# Main.net
KiCad netlist of a schematic drawn in Altium Designer
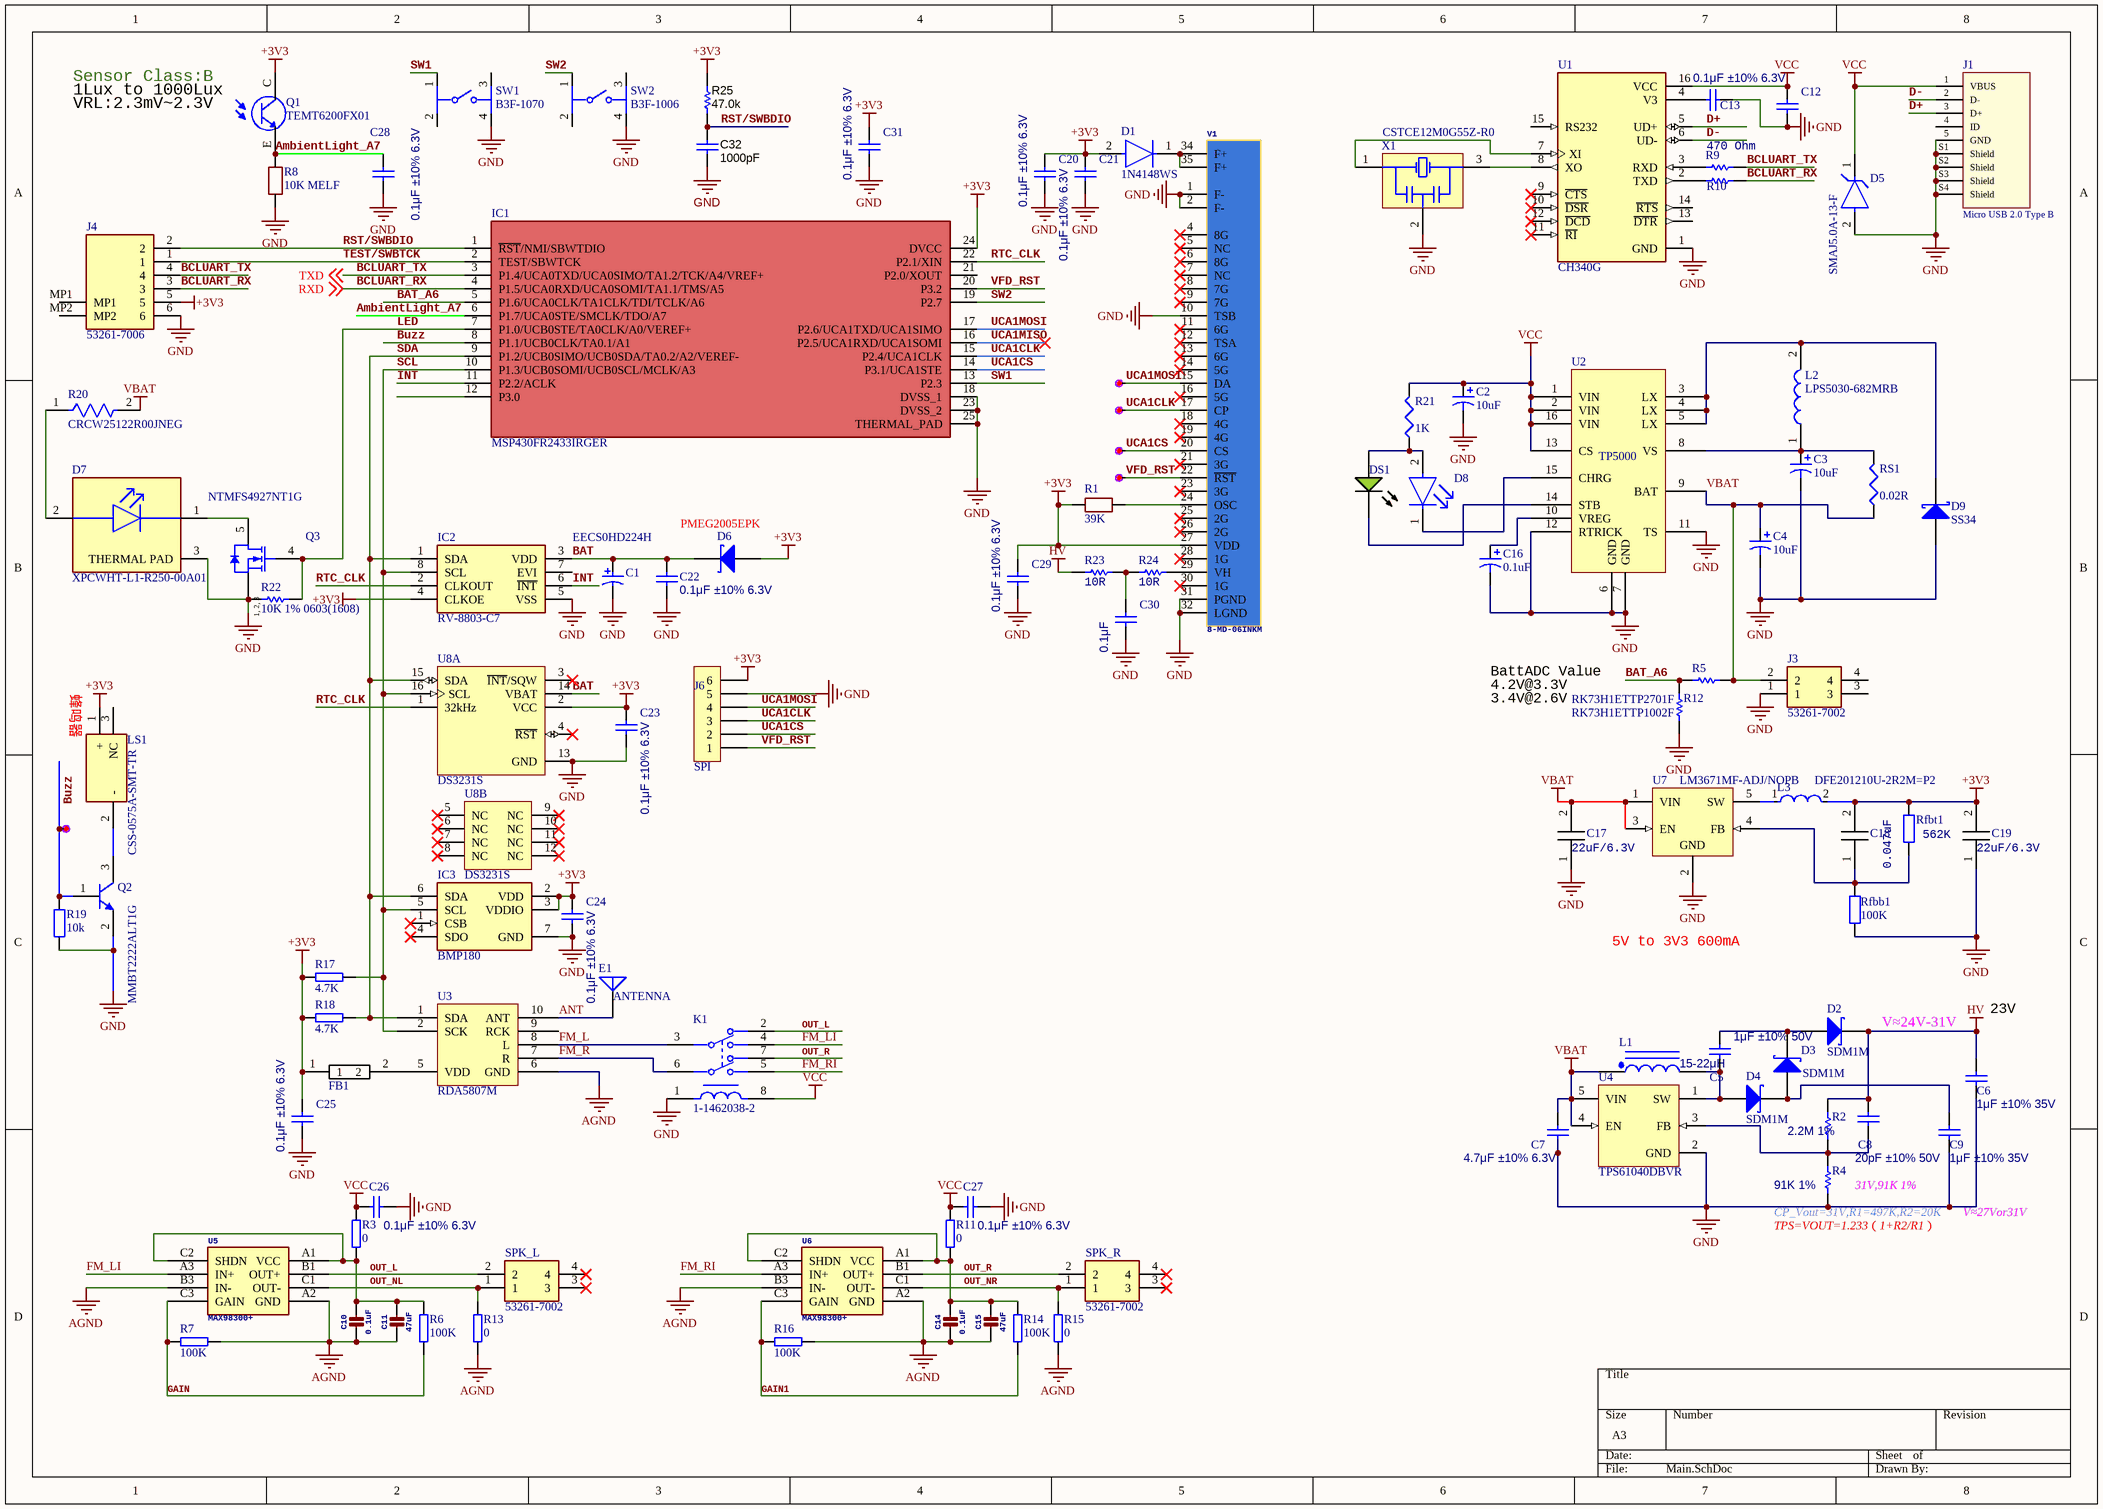
[diagram p0: Main.SchDoc]

(export (version "E")
  (design (tool "Eeschema 10.0.6"))
  (components
    (comp (ref "C1")
      (value "EECS0HD224H")
      (footprint "PNSC-EECS0HD224H")
      (description "Stacked Coin Type Capacitor, 0.22 F, +/- 80%, 5.5 VDC, -25 to 70 degC, 2-Pin THD, RoHS, Bulk")
      (fields (field (name "MANUFACTURER") "Panasonic") (field (name "TOLERANCE") "-20%,+80%"))
      (libsource (lib "Altium Content Vault") (part "CAP-P-2"))
    )
    (comp (ref "C2")
      (value "10uF")
      (footprint "1210")
      (description "Polarized Capacitor (Surface Mount)")
      (fields (field (name "Comment") "Cap Pol3") (field (name "PUBLISHER") "Altium Limited"))
      (libsource (lib "Miscellaneous Devices") (part "Cap Pol3"))
    )
    (comp (ref "C3")
      (value "10uF")
      (footprint "1206")
      (description "Polarized Capacitor (Surface Mount)")
      (fields (field (name "Comment") "Cap Pol3") (field (name "PUBLISHER") "Altium Limited"))
      (libsource (lib "Miscellaneous Devices") (part "Cap Pol3"))
    )
    (comp (ref "C4")
      (value "10uF")
      (footprint "1206")
      (description "Polarized Capacitor (Surface Mount)")
      (fields (field (name "Comment") "Cap Pol3") (field (name "PUBLISHER") "Altium Limited"))
      (libsource (lib "Miscellaneous Devices") (part "Cap Pol3"))
    )
    (comp (ref "C5")
      (value "1μF ±10% 50V")
      (footprint "0402 CAP - s")
      (description "Cap0402,CL05A105KQ5NNNC C52923")
      (libsource (lib "FTJ") (part "Cap SMD"))
    )
    (comp (ref "C6")
      (value "1μF ±10% 35V")
      (footprint "0603 cap - S")
      (description "Cap 0603")
      (libsource (lib "FTJ") (part "Cap SMD"))
    )
    (comp (ref "C7")
      (value "4.7μF ±10% 6.3V")
      (footprint "0402 Cap - S")
      (description "Cap 0603")
      (libsource (lib "FTJ") (part "Cap SMD"))
    )
    (comp (ref "C8")
      (value "20pF ±10% 50V")
      (footprint "0402 CAP - s")
      (description "Cap0402,CL05A105KQ5NNNC C52923")
      (libsource (lib "FTJ") (part "Cap SMD"))
    )
    (comp (ref "C9")
      (value "1μF ±10% 35V")
      (footprint "0402 Cap - S")
      (description "Cap 0603")
      (libsource (lib "FTJ") (part "Cap SMD"))
    )
    (comp (ref "C10")
      (value "0.1uF")
      (footprint "0201")
      (libsource (lib "Metro Mini Rev A") (part "CAP_CERAMIC_0805MP"))
    )
    (comp (ref "C11")
      (value "47uF")
      (footprint "_0805MP")
      (libsource (lib "Metro Mini Rev A") (part "CAP_CERAMIC_0805MP"))
    )
    (comp (ref "C12")
      (value "0.1μF ±10% 6.3V")
      (footprint "0603 cap - S")
      (description "Cap 0603")
      (libsource (lib "FTJ") (part "Cap SMD"))
    )
    (comp (ref "C13")
      (value "0.1μF ±10% 6.3V")
      (footprint "0603 cap - S")
      (description "Cap 0603")
      (libsource (lib "FTJ") (part "Cap SMD"))
    )
    (comp (ref "C14")
      (value "0.1uF")
      (footprint "0201")
      (libsource (lib "Metro Mini Rev A") (part "CAP_CERAMIC_0805MP"))
    )
    (comp (ref "C15")
      (value "47uF")
      (footprint "_0805MP")
      (libsource (lib "Metro Mini Rev A") (part "CAP_CERAMIC_0805MP"))
    )
    (comp (ref "C16")
      (value "0.1uF")
      (footprint "0603")
      (description "Polarized Capacitor (Surface Mount)")
      (fields (field (name "Comment") "Cap Pol3") (field (name "PUBLISHER") "Altium Limited"))
      (libsource (lib "Miscellaneous Devices") (part "Cap Pol3"))
    )
    (comp (ref "C17")
      (value "22uF/6.3V")
      (footprint "0603-CAP")
      (fields
        (field (name "MANUFACTURER_PART_NUMBER") "ZRB18AR61A226ME01L")
        (field (name "Comment") "GRM188R60J226ME15D")
      )
      (libsource (lib "*") (part "ZRB18AR61A226ME01L"))
    )
    (comp (ref "C18")
      (value "0.047uF")
      (footprint "0201")
      (description "CAP, CERM, 0.047uF, 10V, ±10%, X7R, 0201")
      (fields
        (field (name "MANUFACTURER_PART_NUMBER") "GRM155R71E473KA88D")
        (field (name "MOUSER PART NUMBER") "81-GRM155R71E473KA88")
      )
      (libsource (lib "*") (part "GRM155R71E473KA88D"))
    )
    (comp (ref "C19")
      (value "22uF/6.3V")
      (footprint "0603-CAP")
      (fields
        (field (name "MANUFACTURER_PART_NUMBER") "ZRB18AR61A226ME01L")
        (field (name "Comment") "GRM188R60J226ME15D")
      )
      (libsource (lib "*") (part "ZRB18AR61A226ME01L"))
    )
    (comp (ref "C20")
      (value "0.1μF ±10% 6.3V")
      (footprint "0603 cap - S")
      (description "Cap 0603")
      (libsource (lib "FTJ") (part "Cap SMD"))
    )
    (comp (ref "C21")
      (value "0.1μF ±10% 6.3V")
      (footprint "0603 cap - S")
      (description "Cap 0603")
      (libsource (lib "FTJ") (part "Cap SMD"))
    )
    (comp (ref "C22")
      (value "0.1μF ±10% 6.3V")
      (footprint "0603 cap - S")
      (description "Cap 0603")
      (libsource (lib "FTJ") (part "Cap SMD"))
    )
    (comp (ref "C23")
      (value "0.1μF ±10% 6.3V")
      (footprint "0603 cap - S")
      (description "Cap 0603")
      (libsource (lib "FTJ") (part "Cap SMD"))
    )
    (comp (ref "C24")
      (value "0.1μF ±10% 6.3V")
      (footprint "0603 cap - S")
      (description "Cap 0603")
      (libsource (lib "FTJ") (part "Cap SMD"))
    )
    (comp (ref "C25")
      (value "0.1μF ±10% 6.3V")
      (footprint "0603 cap - S")
      (description "Cap 0603")
      (libsource (lib "FTJ") (part "Cap SMD"))
    )
    (comp (ref "C26")
      (value "0.1μF ±10% 6.3V")
      (footprint "0603 cap - S")
      (description "Cap 0603")
      (libsource (lib "FTJ") (part "Cap SMD"))
    )
    (comp (ref "C27")
      (value "0.1μF ±10% 6.3V")
      (footprint "0603 cap - S")
      (description "Cap 0603")
      (libsource (lib "FTJ") (part "Cap SMD"))
    )
    (comp (ref "C28")
      (value "0.1μF ±10% 6.3V")
      (footprint "0603 cap - S")
      (description "Cap 0603")
      (libsource (lib "FTJ") (part "Cap SMD"))
    )
    (comp (ref "C29")
      (value "0.1μF ±10% 6.3V")
      (footprint "0603 cap - S")
      (description "Cap 0603")
      (libsource (lib "FTJ") (part "Cap SMD"))
    )
    (comp (ref "C30")
      (value "0.1μF")
      (footprint "0603 cap - S")
      (description "Cap 0603")
      (libsource (lib "FTJ") (part "Cap SMD"))
    )
    (comp (ref "C31")
      (value "0.1μF ±10% 6.3V")
      (footprint "0603 cap - S")
      (description "Cap 0603")
      (libsource (lib "FTJ") (part "Cap SMD"))
    )
    (comp (ref "C32")
      (value "GRM155R71H102KA01D")
      (footprint "0402")
      (description "CAP, CERM, 1000 pF, 50 V, +/- 10%, X7R, 0402")
      (fields
        (field (name "VALUEDISPLAYED") "1000pF")
        (field (name "MANUFACTURER") "MuRata")
        (field (name "PUBLISHER") "Texas Instruments")
      )
      (libsource (lib "Capacitor_Ceramic") (part "GRM155R71H102KA01D"))
    )
    (comp (ref "D1")
      (value "1N4148WS")
      (footprint "FP-477AB-IPC_C")
      (description "DIODE GEN PURP 75V 150MA SOD323F")
      (libsource (lib "Altium Content Vault") (part "d7152d700b627762746794eb795d46e"))
    )
    (comp (ref "D2")
      (value "SDM1M")
      (footprint "DFN1608-2-UDFN1608")
      (description "Schotty Diodes")
      (libsource (lib "FTJ") (part "Diode_Schotty"))
    )
    (comp (ref "D3")
      (value "SDM1M")
      (footprint "DFN1608-2-UDFN1608")
      (description "Schotty Diodes")
      (libsource (lib "FTJ") (part "Diode_Schotty"))
    )
    (comp (ref "D4")
      (value "SDM1M")
      (footprint "DFN1608-2-UDFN1608")
      (description "Schotty Diodes")
      (libsource (lib "FTJ") (part "Diode_Schotty"))
    )
    (comp (ref "D5")
      (value "SMAJ5.0A-13-F")
      (footprint "FP-SMA-MFG")
      (description "TVS DIODE 5V 9.2V SMA")
      (fields
        (field (name "MANUFACTURER") "Diodes Inc.")
        (field (name "OCTOPART") "https://octopart.com/smaj5.0a-13-f-diodes+inc.-350158")
      )
      (libsource (lib "Altium Content Vault") (part "f813f71cba58e380607f5dd3caf9714"))
    )
    (comp (ref "D6")
      (value "PMEG2005EPK")
      (footprint "DFN1608-2-UDFN1608")
      (description "Schotty Diodes")
      (libsource (lib "FTJ") (part "Diode_Schotty"))
    )
    (comp (ref "D7")
      (value "XPCWHT-L1-R250-00A01")
      (footprint "FP-XPCWHT-MFG")
      (description "LED XLAMP COOL WHITE 70CRI 2SMD")
      (fields
        (field (name "OCTOPART") "https://octopart.com/xpcwht-l1-r250-00a01-cree-9519579")
        (field (name "MANUFACTURER") "Cree Inc.")
      )
      (libsource (lib "Altium Content Vault") (part "a9d0dd8659a82a27d4251d925192800"))
    )
    (comp (ref "D8")
      (value "VLMW1300-GS08")
      (footprint "FP-6_541-5091_01-4-MFG")
      (description "LED COOL WHITE 0603 SMD")
      (fields
        (field (name "MANUFACTURER") "Vishay")
        (field (name "OCTOPART") "https://octopart.com/vlmw1300-gs08-vishay-21709203")
      )
      (libsource (lib "Altium Content Vault") (part "8706943c75ba83719d021d2fdc84c58"))
    )
    (comp (ref "D9")
      (value "SS34")
      (footprint "SMB")
      (description "Schottky Diode")
      (fields (field (name "PUBLISHER") "Altium Limited"))
      (libsource (lib "Miscellaneous Devices") (part "D Schottky"))
    )
    (comp (ref "DS1")
      (value "ASMT-RF45-AN002")
      (footprint "AVAG-ASMT-RF45_V")
      (description "LED Yellow - Green, 48 mW, 20 mA, -40 to 100 degC, 2-Pin SMD, RoHS, Tape and Reel")
      (fields (field (name "MANUFACTURER") "Avago"))
      (libsource (lib "Altium Content Vault") (part "LED-YELLOW-GREEN-AK-2"))
    )
    (comp (ref "E1")
      (value "ANTENNA")
      (footprint "P125-B")
      (description "Generic Antenna")
      (libsource (lib "Integrated_Library1") (part "ANTENNA"))
    )
    (comp (ref "FB1")
      (value "MPZ1608S260ATAH0")
      (footprint "BEADC1608X75N")
      (description "Ferrite Bead")
      (fields (field (name "MOUSER PART NUMBER") "810-MPZ1608S260ATAH0"))
      (libsource (lib "STM32F405 general control board_1") (part "MPZ1608S260ATAH0"))
    )
    (comp (ref "IC1")
      (value "MSP430FR2433IRGER")
      (footprint "SamacSys:QFN50P400X400X100-25N-D")
      (description "Integrated Circuit")
      (fields (field (name "MOUSER PART NUMBER") "595-SP430FR2433IRGER"))
      (libsource (lib "SamacSys") (part "MSP430FR2433IRGER"))
    )
    (comp (ref "IC2")
      (value "RV-8803-C7")
      (footprint "SamacSys:RV8803C7")
      (description "Integrated Circuit")
      (libsource (lib "*") (part "RV-8803-C7"))
    )
    (comp (ref "IC3")
      (value "BMP180")
      (footprint "SamacSys:BMP180")
      (description "Integrated Circuit")
      (fields (field (name "MOUSER PART NUMBER") "262-BMP180"))
      (libsource (lib "*") (part "BMP180"))
    )
    (comp (ref "J1")
      (value "Micro USB 2.0 Type B")
      (footprint "629105136821")
      (description "Micro USB 2.0 Type B Horizontal SMT 5 Contacts WR-COM")
      (fields (field (name "PART NUMBER") "629105136821") (field (name "PUBLISHER") "Wurth Elektronik"))
      (libsource (lib "ALTIUM-WR-COM-rev18a") (part "629105136821"))
    )
    (comp (ref "J3")
      (value "53261-7002")
      (footprint "SamacSys:532617002")
      (description "Connector")
      (fields (field (name "MOUSER PART NUMBER") "538-53261-7002"))
      (libsource (lib "*") (part "53261-7002"))
    )
    (comp (ref "J4")
      (value "53261-7006")
      (footprint "MX 1.25-WS-6P")
      (description "Connector")
      (fields (field (name "MOUSER PART NUMBER") "538-53261-7006"))
      (libsource (lib "*") (part "53261-7006"))
    )
    (comp (ref "J6")
      (value "SPI")
      (footprint "SIP6")
      (description "Connector")
      (libsource (lib "9G_SCH") (part "CON6"))
    )
    (comp (ref "K1")
      (value "1-1462038-2")
      (footprint "FP-1-1462038-2-MFG")
      (description "RELAY TELECOM DPDT 2A 4.5V")
      (fields
        (field (name "MANUFACTURER") "TE Connectivity")
        (field (name "OCTOPART") "https://octopart.com/1-1462038-2-te+connectivity-40642255")
      )
      (libsource (lib "Altium Content Vault") (part "f6f6c627aadb73ad41e05903558ffa9"))
    )
    (comp (ref "L1")
      (value "15-22μH")
      (footprint "NRS4012")
      (description "Magnetic-Core Inductor with Winding Polarity Marking")
      (fields (field (name "Comment") "Inductor Iron Dot") (field (name "PUBLISHER") "Altium Limited"))
      (libsource (lib "FTJ") (part "Inductor Iron Dot"))
    )
    (comp (ref "L2")
      (value "LPS5030-682MRB")
      (footprint "RCDQLY:LPS5030")
      (description "Inductor")
      (fields
        (field (name "MANUFACTURER_PART_NUMBER") "LPS5030-562MRB")
        (field (name "MOUSER PART NUMBER") "994-LPS5030-562MRB")
      )
      (libsource (lib "*") (part "LPS5030-562MRB"))
    )
    (comp (ref "L3")
      (value "DFE201210U-2R2M=P2")
      (footprint "FP-DFE201210U-MFG")
      (description "FIXED IND 2.2UH 1.2A 228 MOHM")
      (libsource (lib "Altium Content Vault") (part "725321dda6339637d4d059423bc1c3c"))
    )
    (comp (ref "LS1")
      (value "CSS-0575A-SMT-TR")
      (footprint "SamacSys:CSS0575ASMTTR")
      (description "Loudspeaker or Buzzer")
      (fields (field (name "MOUSER PART NUMBER") "490-CSS-0575A-SMT-TR"))
      (libsource (lib "*") (part "CSS-0575A-SMT-TR"))
    )
    (comp (ref "Q1")
      (value "TEMT6200FX01")
      (footprint "TEMT6200FX01:XDCR_TEMT6200FX01")
      (description "Phototransistors 550nm Top View 0805 (2012 Metric)")
      (fields (field (name "MF") "{'manufacturer': u'Vishay Semiconductor Opto Division'}"))
      (libsource (lib "*") (part "TEMT6200FX01"))
    )
    (comp (ref "Q2")
      (value "MMBT2222ALT1G")
      (footprint "ONSC-SOT-23-3-318-08_V")
      (description "General Purpose Transistor, NPN Silicon, 3-Pin SOT-23, Pb-Free, Tape and Reel")
      (fields (field (name "MANUFACTURER") "On Semiconductor"))
      (libsource (lib "Altium Content Vault") (part "ONSC-NPN-B1E2C3-3"))
    )
    (comp (ref "Q3")
      (value "NTMFS4927NT1G")
      (footprint "ONSC-DFN-5-488AA_V")
      (description "Power MOSFET, 30 V, 38 A, Single N-Channel, 5-Pin DFN, Pb-Free, Tape and Reel")
      (fields (field (name "MANUFACTURER") "On Semiconductor"))
      (libsource (lib "Altium Content Vault") (part "ONSC-NMOS-6_E"))
    )
    (comp (ref "R1")
      (value "39K")
      (footprint "MELF1")
      (description "Resistor")
      (libsource (lib "") (part "RES2_1"))
    )
    (comp (ref "R2")
      (value "2.2M 1%")
      (footprint "0402 res - s")
      (description "Resistor C11702")
      (fields (field (name "PUBLISHER") "Altium Limited"))
      (libsource (lib "Miscellaneous Devices") (part "Res1"))
    )
    (comp (ref "R3")
      (value "0")
      (footprint "0603")
      (description "Resistor")
      (libsource (lib "9G_SCH") (part "RES2"))
    )
    (comp (ref "R4")
      (value "91K 1%")
      (footprint "0402 res - s")
      (description "Resistor C11702")
      (fields (field (name "PUBLISHER") "Altium Limited"))
      (libsource (lib "Miscellaneous Devices") (part "Res1"))
    )
    (comp (ref "R5")
      (value "RK73H1ETTP2701F")
      (footprint "RESC1005X40X25LL10T10")
      (fields (field (name "MANUFACTURER") "KOA Speer"))
      (libsource (lib "Altium Content Vault") (part "RES"))
    )
    (comp (ref "R6")
      (value "100K")
      (footprint "0201")
      (description "Resistor")
      (libsource (lib "9G_SCH") (part "RES2"))
    )
    (comp (ref "R7")
      (value "100K")
      (footprint "0201")
      (description "Resistor")
      (libsource (lib "9G_SCH") (part "RES2"))
    )
    (comp (ref "R8")
      (value "10K MELF")
      (footprint "MELF-R3216-1206")
      (description "Resistor")
      (libsource (lib "") (part "RES2_1"))
    )
    (comp (ref "R9")
      (value "RC0603FR-07470RL")
      (footprint "RESC1608X55X25LL10T15")
      (fields (field (name "RESISTANCE") "470 Ohm"))
      (libsource (lib "Altium Content Vault") (part "RES-2"))
    )
    (comp (ref "R10")
      (value "RC0603FR-07470RL")
      (footprint "RESC1608X55X25LL10T15")
      (libsource (lib "Altium Content Vault") (part "RES-2"))
    )
    (comp (ref "R11")
      (value "0")
      (footprint "0603")
      (description "Resistor")
      (libsource (lib "9G_SCH") (part "RES2"))
    )
    (comp (ref "R12")
      (value "RK73H1ETTP1002F")
      (footprint "RESC1005X40X25NL10T10")
      (fields (field (name "MANUFACTURER") "KOA Speer"))
      (libsource (lib "Altium Content Vault") (part "RES"))
    )
    (comp (ref "R13")
      (value "0")
      (footprint "0201")
      (description "Resistor")
      (libsource (lib "9G_SCH") (part "RES2"))
    )
    (comp (ref "R14")
      (value "100K")
      (footprint "0201")
      (description "Resistor")
      (libsource (lib "9G_SCH") (part "RES2"))
    )
    (comp (ref "R15")
      (value "0")
      (footprint "0201")
      (description "Resistor")
      (libsource (lib "9G_SCH") (part "RES2"))
    )
    (comp (ref "R16")
      (value "100K")
      (footprint "0201")
      (description "Resistor")
      (libsource (lib "9G_SCH") (part "RES2"))
    )
    (comp (ref "R17")
      (value "4.7K")
      (footprint "0603")
      (description "Resistor")
      (libsource (lib "9G_SCH") (part "RES2"))
    )
    (comp (ref "R18")
      (value "4.7K")
      (footprint "0603")
      (description "Resistor")
      (libsource (lib "9G_SCH") (part "RES2"))
    )
    (comp (ref "R19")
      (value "10k")
      (footprint "0603 RES")
      (description "贴片电阻")
      (fields (field (name "版权归属") "源创客"))
      (libsource (lib "3.1   - 电阻-电容-电感") (part "R"))
    )
    (comp (ref "R20")
      (value "CRCW25122R00JNEG")
      (footprint "FP-CRCW2512-e3-IPC_C")
      (description "RES Thick Film, 2Ω, 5%, 1W, 200ppm/°C, 2512")
      (fields (field (name "TOLERANCE") "5%"))
      (libsource (lib "Altium Content Vault") (part "1029c3af85768c4190bb7ad29bc67b5"))
    )
    (comp (ref "R21")
      (value "1K")
      (footprint "0603")
      (description "Resistor")
      (fields (field (name "PUBLISHER") "Altium Limited"))
      (libsource (lib "Miscellaneous Devices") (part "Res3"))
    )
    (comp (ref "R22")
      (value "10K 1% 0603(1608)")
      (footprint "RESC0603(1608)_N")
      (description "10K 0.1W 1% 0603 (1608 Metric)  SMD")
      (fields (field (name "POWER") "0.1 W") (field (name "TOLERANCE") "1 %"))
      (libsource (lib "Altium Content Vault") (part "RES"))
    )
    (comp (ref "R23")
      (value "TNPW060310R0BEEA")
      (footprint "RESC1609X55X30NL10T20")
      (fields (field (name "MANUFACTURER") "Vishay Dale") (field (name "PARAMETER 1") "10R"))
      (libsource (lib "Altium Content Vault") (part "RES"))
    )
    (comp (ref "R24")
      (value "TNPW060310R0BEEA")
      (footprint "RESC1609X55X30NL10T20")
      (fields (field (name "MANUFACTURER") "Vishay Dale") (field (name "PARAMETER 1") "10R"))
      (libsource (lib "Altium Content Vault") (part "RES"))
    )
    (comp (ref "R25")
      (value "RC0402FR-0747KL")
      (footprint "0402")
      (description "RES, 47.0 k, 1%, 0.0625 W, 0402")
      (fields
        (field (name "VALUEDISPLAYED") "47.0k")
        (field (name "MANUFACTURER") "Yageo America")
        (field (name "PUBLISHER") "Texas Instruments")
      )
      (libsource (lib "Resistor_0402") (part "RC0402FR-0747KL"))
    )
    (comp (ref "Rfbb1")
      (value "100K")
      (footprint "0201")
      (description "SMD 1/10Watt 100Kohms 1%")
      (fields (field (name "Comment") "RC0201JR-13100KL"))
      (libsource (lib "Miscellaneous Devices LC") (part "0603 82KΩ (8202) 1%"))
    )
    (comp (ref "Rfbt1")
      (value "RC0201FR-07309KL")
      (footprint "0201")
      (description "贴片电阻562K")
      (fields (field (name "PARAMETER 1") "562K"))
      (libsource (lib "3.1   - 电阻-电容-电感") (part "R"))
    )
    (comp (ref "RS1")
      (value "0.02R")
      (footprint "1206")
      (description "Resistor")
      (fields (field (name "PUBLISHER") "Altium Limited"))
      (libsource (lib "Miscellaneous Devices") (part "Res3"))
    )
    (comp (ref "SPK_L")
      (value "53261-7002")
      (footprint "SamacSys:532617002")
      (description "Connector")
      (fields (field (name "MOUSER PART NUMBER") "538-53261-7002"))
      (libsource (lib "*") (part "53261-7002"))
    )
    (comp (ref "SPK_R")
      (value "53261-7002")
      (footprint "SamacSys:532617002")
      (description "Connector")
      (fields (field (name "MOUSER PART NUMBER") "538-53261-7002"))
      (libsource (lib "*") (part "53261-7002"))
    )
    (comp (ref "SW1")
      (value "B3F-1070")
      (footprint "FP-B3F-1070-MFG")
      (description "SWITCH TACTILE SPST-NO 0.05A 24V")
      (libsource (lib "Altium Content Vault") (part "b8895f3f4cefb76e1819d2863dba89b"))
    )
    (comp (ref "SW2")
      (value "B3F-1006")
      (footprint "FP-B3F-1006-MFG")
      (description "SWITCH TACTILE SPST-NO 0.05A 24V")
      (libsource (lib "Altium Content Vault") (part "b8895f3f4cefb76e1819d2863dba89b"))
    )
    (comp (ref "TP1")
      (value "Buzz")
      (footprint "TestPoint-SMT 0.8MM")
      (description "IC-DS1_DIS_GND")
      (libsource (lib "LightArx-Zeus-Boards-RFPCB_Ver0.01e") (part "TestPoint_SMT_11"))
    )
    (comp (ref "TP2")
      (value "Buzz")
      (footprint "TestPoint-SMT 0.8MM")
      (description "IC-DS1_DIS_GND")
      (libsource (lib "LightArx-Zeus-Boards-RFPCB_Ver0.01e") (part "TestPoint_SMT_11"))
    )
    (comp (ref "TP3")
      (value "Buzz")
      (footprint "TestPoint-SMT 0.8MM")
      (description "IC-DS1_DIS_GND")
      (libsource (lib "LightArx-Zeus-Boards-RFPCB_Ver0.01e") (part "TestPoint_SMT_11"))
    )
    (comp (ref "TP4")
      (value "Buzz")
      (footprint "TestPoint-SMT 0.8MM")
      (description "IC-DS1_DIS_GND")
      (libsource (lib "LightArx-Zeus-Boards-RFPCB_Ver0.01e") (part "TestPoint_SMT_11"))
    )
    (comp (ref "TP5")
      (value "Buzz")
      (footprint "TestPoint-SMT 0.8MM")
      (description "IC-DS1_DIS_GND")
      (libsource (lib "LightArx-Zeus-Boards-RFPCB_Ver0.01e") (part "TestPoint_SMT_11"))
    )
    (comp (ref "U1")
      (value "CH340G")
      (footprint "Ch340G:SOIC127P600X180-16N")
      (fields (field (name "MF") "{'manufacturer': u'WCH'}"))
      (libsource (lib "*") (part "CH340G"))
    )
    (comp (ref "U2") (value "TP5000") (footprint "QFN-16") (libsource (lib "TP5000") (part "TP5000")))
    (comp (ref "U3") (value "RDA5807M") (footprint "RDA5807M") (libsource (lib "9G_SCH") (part "RDA5807M")))
    (comp (ref "U4")
      (value "TPS61040DBVR")
      (footprint "DBV0005A_N")
      (fields (field (name "MANUFACTURER") "Texas Instruments"))
      (libsource (lib "Altium Content Vault") (part "TI-TPS61040DBV5"))
    )
    (comp (ref "U5")
      (value "MAX98300+")
      (footprint "WLP-9")
      (description "Mono 2.6W ClassD Amp.")
      (libsource (lib "9G_SCH") (part "MAX98300+"))
    )
    (comp (ref "U6")
      (value "MAX98300+")
      (footprint "WLP-9")
      (description "Mono 2.6W ClassD Amp.")
      (libsource (lib "9G_SCH") (part "MAX98300+"))
    )
    (comp (ref "U7")
      (value "LM3671MF-ADJ/NOPB")
      (footprint "DBV0005A_N")
      (description "2MHz, 600mA Step-Down DC-DC Converter, 5-pin SOT-23, Pb-Free")
      (fields (field (name "MANUFACTURER") "Texas Instruments"))
      (libsource (lib "Altium Content Vault") (part "PM-DCDC-LM3670-5"))
    )
    (comp (ref "U8")
      (value "DS3231S")
      (footprint "W16-H2_L")
      (description "Extremely Accurate I2C-Integrated Real-Time Clock/TCXO/Crystal, 16-Pin SO, 0 to 70 degC")
      (libsource (lib "") (part "MAX-RTC-16-DS3231S-W16#H2_1"))
    )
    (comp (ref "V1")
      (value "8-MD-06INKM")
      (footprint "Futaba 8-MD6INKM")
      (description "8 BIT VFD")
      (libsource (lib "9G_SCH") (part "8-MD-06INKM"))
    )
    (comp (ref "X1")
      (value "CSTCE12M0G55Z-R0")
      (footprint "MURA-CSTCE_G_V")
      (description "Ceramic Resonator, 12 MHz, +/- 0.5%, -40 to 125 degC, 3-Pin SMD, RoHS, Tape and Reel")
      (fields (field (name "MANUFACTURER") "Murata"))
      (libsource (lib "Altium Content Vault") (part "MURA-CSTCE_G_A-3"))
    )
  )
  (nets
    (net (code "1") (name "+3V3") (class "Default")
      (node (ref "C18") (pin "2") (pinfunction "2_2") (pintype "passive"))
      (node (ref "C19") (pin "2") (pinfunction "2_2") (pintype "passive"))
      (node (ref "C20") (pin "2") (pinfunction "2_2") (pintype "passive"))
      (node (ref "C21") (pin "2") (pinfunction "2_2") (pintype "passive"))
      (node (ref "C23") (pin "2") (pinfunction "2_2") (pintype "passive"))
      (node (ref "C24") (pin "2") (pinfunction "2_2") (pintype "passive"))
      (node (ref "C25") (pin "2") (pinfunction "2_2") (pintype "passive"))
      (node (ref "C29") (pin "2") (pinfunction "2_2") (pintype "passive"))
      (node (ref "C31") (pin "2") (pinfunction "2_2") (pintype "passive"))
      (node (ref "D1") (pin "2") (pinfunction "A_2") (pintype "passive"))
      (node (ref "D6") (pin "A") (pinfunction "A_A") (pintype "passive"))
      (node (ref "FB1") (pin "1") (pinfunction "1_1") (pintype "passive"))
      (node (ref "IC1") (pin "24") (pinfunction "DVCC_24") (pintype "passive"))
      (node (ref "IC2") (pin "4") (pinfunction "CLKOE_4") (pintype "passive"))
      (node (ref "IC3") (pin "2") (pinfunction "VDD_2") (pintype "power_in"))
      (node (ref "IC3") (pin "3") (pinfunction "VDDIO_3") (pintype "power_in"))
      (node (ref "J4") (pin "5") (pinfunction "5_5") (pintype "passive"))
      (node (ref "J6") (pin "6") (pinfunction "6_6") (pintype "passive"))
      (node (ref "L3") (pin "2") (pinfunction "2_2") (pintype "passive"))
      (node (ref "LS1") (pin "1") (pinfunction "+_1") (pintype "passive"))
      (node (ref "Q1") (pin "C") (pinfunction "C_C") (pintype "passive"))
      (node (ref "R1") (pin "2") (pinfunction "2_2") (pintype "passive"))
      (node (ref "R17") (pin "2") (pinfunction "2_2") (pintype "passive"))
      (node (ref "R18") (pin "2") (pinfunction "2_2") (pintype "passive"))
      (node (ref "R25") (pin "2") (pinfunction "2_2") (pintype "passive"))
      (node (ref "Rfbt1") (pin "1") (pinfunction "1_1") (pintype "passive"))
      (node (ref "U8") (pin "2") (pinfunction "VCC_2") (pintype "power_in"))
      (node (ref "V1") (pin "27") (pinfunction "VDD_27") (pintype "power_in"))
    )
    (net (code "2") (name "/ANT") (class "Default")
      (node (ref "E1") (pin "1") (pinfunction "A_1") (pintype "passive"))
      (node (ref "U3") (pin "10") (pinfunction "ANT_10") (pintype "passive"))
    )
    (net (code "3") (name "/AmbientLight_A7") (class "Default")
      (node (ref "C28") (pin "2") (pinfunction "2_2") (pintype "passive"))
      (node (ref "IC1") (pin "6") (pinfunction "P1.7/UCA0STE/SMCLK/TDO/A7_6") (pintype "passive"))
      (node (ref "Q1") (pin "E") (pinfunction "E_E") (pintype "passive"))
      (node (ref "R8") (pin "2") (pinfunction "2_2") (pintype "passive"))
    )
    (net (code "4") (name "/BAT") (class "Default")
      (node (ref "C1") (pin "1") (pinfunction "1_1") (pintype "passive"))
      (node (ref "C22") (pin "2") (pinfunction "2_2") (pintype "passive"))
      (node (ref "D6") (pin "K") (pinfunction "K_K") (pintype "passive"))
      (node (ref "IC2") (pin "3") (pinfunction "VDD_3") (pintype "passive"))
      (node (ref "U8") (pin "14") (pinfunction "VBAT_14") (pintype "power_in"))
    )
    (net (code "5") (name "/BAT_A6") (class "Default")
      (node (ref "IC1") (pin "5") (pinfunction "P1.6/UCA0CLK/TA1CLK/TDI/TCLK/A6_5") (pintype "passive"))
      (node (ref "R12") (pin "2") (pinfunction "2_2") (pintype "passive"))
      (node (ref "R5") (pin "1") (pinfunction "1_1") (pintype "passive"))
    )
    (net (code "6") (name "/Buzz") (class "Default")
      (node (ref "IC1") (pin "8") (pinfunction "P1.1/UCB0CLK/TA0.1/A1_8") (pintype "passive"))
      (node (ref "Q2") (pin "1") (pinfunction "B_1") (pintype "passive"))
      (node (ref "R19") (pin "1") (pinfunction "1_1") (pintype "passive"))
      (node (ref "TP1") (pin "1") (pinfunction "1_1") (pintype "passive"))
    )
    (net (code "7") (name "/D+") (class "Default")
      (node (ref "J1") (pin "3") (pinfunction "D+_3") (pintype "passive"))
      (node (ref "U1") (pin "5") (pinfunction "UD+_5") (pintype "bidirectional"))
    )
    (net (code "8") (name "/D-") (class "Default")
      (node (ref "J1") (pin "2") (pinfunction "D-_2") (pintype "passive"))
      (node (ref "U1") (pin "6") (pinfunction "UD-_6") (pintype "bidirectional"))
    )
    (net (code "9") (name "/FM_L") (class "Default")
      (node (ref "K1") (pin "3") (pinfunction "3_3") (pintype "passive"))
      (node (ref "U3") (pin "8") (pinfunction "L_8") (pintype "passive"))
    )
    (net (code "10") (name "/FM_LI") (class "Default")
      (node (ref "K1") (pin "4") (pinfunction "4_4") (pintype "passive"))
      (node (ref "U5") (pin "A3") (pinfunction "IN+_A3") (pintype "passive"))
    )
    (net (code "11") (name "/FM_R") (class "Default")
      (node (ref "K1") (pin "6") (pinfunction "6_6") (pintype "passive"))
      (node (ref "U3") (pin "7") (pinfunction "R_7") (pintype "passive"))
    )
    (net (code "12") (name "/FM_RI") (class "Default")
      (node (ref "K1") (pin "5") (pinfunction "5_5") (pintype "passive"))
      (node (ref "U6") (pin "A3") (pinfunction "IN+_A3") (pintype "passive"))
    )
    (net (code "13") (name "/GAIN") (class "Default")
      (node (ref "R6") (pin "2") (pinfunction "2_2") (pintype "passive"))
      (node (ref "R7") (pin "1") (pinfunction "1_1") (pintype "passive"))
      (node (ref "U5") (pin "C3") (pinfunction "GAIN_C3") (pintype "passive"))
    )
    (net (code "14") (name "/GAIN1") (class "Default")
      (node (ref "R14") (pin "2") (pinfunction "2_2") (pintype "passive"))
      (node (ref "R16") (pin "1") (pinfunction "1_1") (pintype "passive"))
      (node (ref "U6") (pin "C3") (pinfunction "GAIN_C3") (pintype "passive"))
    )
    (net (code "15") (name "/INT") (class "Default")
      (node (ref "IC1") (pin "11") (pinfunction "P2.2/ACLK_11") (pintype "passive"))
      (node (ref "IC2") (pin "6") (pinfunction "~{INT}_6") (pintype "passive"))
    )
    (net (code "16") (name "/LED") (class "Default")
      (node (ref "IC1") (pin "7") (pinfunction "P1.0/UCB0STE/TA0CLK/A0/VEREF+_7") (pintype "passive"))
      (node (ref "Q3") (pin "4") (pinfunction "G_4") (pintype "passive"))
      (node (ref "R22") (pin "2") (pinfunction "2_2") (pintype "passive"))
    )
    (net (code "17") (name "/OUT_L") (class "Default")
      (node (ref "K1") (pin "2") (pinfunction "2_2") (pintype "passive"))
      (node (ref "SPK_L") (pin "2") (pinfunction "2_2") (pintype "passive"))
      (node (ref "U5") (pin "B1") (pinfunction "OUT+_B1") (pintype "passive"))
    )
    (net (code "18") (name "/OUT_NL") (class "Default")
      (node (ref "R13") (pin "1") (pinfunction "1_1") (pintype "passive"))
      (node (ref "SPK_L") (pin "1") (pinfunction "1_1") (pintype "passive"))
      (node (ref "U5") (pin "C1") (pinfunction "OUT-_C1") (pintype "passive"))
    )
    (net (code "19") (name "/OUT_NR") (class "Default")
      (node (ref "R15") (pin "1") (pinfunction "1_1") (pintype "passive"))
      (node (ref "SPK_R") (pin "1") (pinfunction "1_1") (pintype "passive"))
      (node (ref "U6") (pin "C1") (pinfunction "OUT-_C1") (pintype "passive"))
    )
    (net (code "20") (name "/OUT_R") (class "Default")
      (node (ref "K1") (pin "7") (pinfunction "7_7") (pintype "passive"))
      (node (ref "SPK_R") (pin "2") (pinfunction "2_2") (pintype "passive"))
      (node (ref "U6") (pin "B1") (pinfunction "OUT+_B1") (pintype "passive"))
    )
    (net (code "21") (name "/RST{slash}SWBDIO") (class "Default")
      (node (ref "C32") (pin "1") (pinfunction "1_1") (pintype "passive"))
      (node (ref "IC1") (pin "1") (pinfunction "~{RST}/NMI/SBWTDIO_1") (pintype "passive"))
      (node (ref "J4") (pin "2") (pinfunction "2_2") (pintype "passive"))
      (node (ref "R25") (pin "1") (pinfunction "1_1") (pintype "passive"))
    )
    (net (code "22") (name "/RTC_CLK") (class "Default")
      (node (ref "IC1") (pin "22") (pinfunction "P2.1/XIN_22") (pintype "passive"))
      (node (ref "IC2") (pin "2") (pinfunction "CLKOUT_2") (pintype "passive"))
      (node (ref "U8") (pin "1") (pinfunction "32kHz_1") (pintype "open_collector"))
    )
    (net (code "23") (name "/SCL") (class "Default")
      (node (ref "IC1") (pin "10") (pinfunction "P1.3/UCB0SOMI/UCB0SCL/MCLK/A3_10") (pintype "passive"))
      (node (ref "IC2") (pin "8") (pinfunction "SCL_8") (pintype "passive"))
      (node (ref "IC3") (pin "5") (pinfunction "SCL_5") (pintype "passive"))
      (node (ref "R17") (pin "1") (pinfunction "1_1") (pintype "passive"))
      (node (ref "U3") (pin "2") (pinfunction "SCK_2") (pintype "passive"))
      (node (ref "U8") (pin "16") (pinfunction "SCL_16") (pintype "input"))
    )
    (net (code "24") (name "/SDA") (class "Default")
      (node (ref "IC1") (pin "9") (pinfunction "P1.2/UCB0SIMO/UCB0SDA/TA0.2/A2/VEREF-_9") (pintype "passive"))
      (node (ref "IC2") (pin "1") (pinfunction "SDA_1") (pintype "passive"))
      (node (ref "IC3") (pin "6") (pinfunction "SDA_6") (pintype "passive"))
      (node (ref "R18") (pin "1") (pinfunction "1_1") (pintype "passive"))
      (node (ref "U3") (pin "1") (pinfunction "SDA_1") (pintype "passive"))
      (node (ref "U8") (pin "15") (pinfunction "SDA_15") (pintype "bidirectional"))
    )
    (net (code "25") (name "/SW1") (class "Default")
      (node (ref "IC1") (pin "13") (pinfunction "P2.3_13") (pintype "passive"))
      (node (ref "SW1") (pin "1") (pinfunction "1_1") (pintype "passive"))
    )
    (net (code "26") (name "/SW2") (class "Default")
      (node (ref "IC1") (pin "19") (pinfunction "P2.7_19") (pintype "passive"))
      (node (ref "SW2") (pin "1") (pinfunction "1_1") (pintype "passive"))
    )
    (net (code "27") (name "/TEST{slash}SWBTCK") (class "Default")
      (node (ref "IC1") (pin "2") (pinfunction "TEST/SBWTCK_2") (pintype "passive"))
      (node (ref "J4") (pin "1") (pinfunction "1_1") (pintype "passive"))
    )
    (net (code "28") (name "/UCA1CLK") (class "Default")
      (node (ref "IC1") (pin "15") (pinfunction "P2.4/UCA1CLK_15") (pintype "passive"))
      (node (ref "J6") (pin "3") (pinfunction "3_3") (pintype "passive"))
      (node (ref "TP3") (pin "1") (pinfunction "1_1") (pintype "passive"))
      (node (ref "V1") (pin "17") (pinfunction "CP_17") (pintype "power_in"))
    )
    (net (code "29") (name "/UCA1CS") (class "Default")
      (node (ref "IC1") (pin "14") (pinfunction "P3.1/UCA1STE_14") (pintype "passive"))
      (node (ref "J6") (pin "2") (pinfunction "2_2") (pintype "passive"))
      (node (ref "TP4") (pin "1") (pinfunction "1_1") (pintype "passive"))
      (node (ref "V1") (pin "20") (pinfunction "CS_20") (pintype "power_in"))
    )
    (net (code "30") (name "/UCA1MISO") (class "Default")
      (node (ref "IC1") (pin "16") (pinfunction "P2.5/UCA1RXD/UCA1SOMI_16") (pintype "passive+no_connect"))
    )
    (net (code "31") (name "/UCA1MOSI") (class "Default")
      (node (ref "IC1") (pin "17") (pinfunction "P2.6/UCA1TXD/UCA1SIMO_17") (pintype "passive"))
      (node (ref "J6") (pin "4") (pinfunction "4_4") (pintype "passive"))
      (node (ref "TP2") (pin "1") (pinfunction "1_1") (pintype "passive"))
      (node (ref "V1") (pin "15") (pinfunction "DA_15") (pintype "power_in"))
    )
    (net (code "32") (name "/VFD_RST") (class "Default")
      (node (ref "IC1") (pin "20") (pinfunction "P3.2_20") (pintype "passive"))
      (node (ref "J6") (pin "1") (pinfunction "1_1") (pintype "passive"))
      (node (ref "TP5") (pin "1") (pinfunction "1_1") (pintype "passive"))
      (node (ref "V1") (pin "22") (pinfunction "~{RST}_22") (pintype "power_in"))
    )
    (net (code "33") (name "AGND") (class "Default")
      (node (ref "C10") (pin "2") (pinfunction "2_2") (pintype "passive"))
      (node (ref "C11") (pin "2") (pinfunction "2_2") (pintype "passive"))
      (node (ref "C14") (pin "2") (pinfunction "2_2") (pintype "passive"))
      (node (ref "C15") (pin "2") (pinfunction "2_2") (pintype "passive"))
      (node (ref "R13") (pin "2") (pinfunction "2_2") (pintype "passive"))
      (node (ref "R15") (pin "2") (pinfunction "2_2") (pintype "passive"))
      (node (ref "R16") (pin "2") (pinfunction "2_2") (pintype "passive"))
      (node (ref "R7") (pin "2") (pinfunction "2_2") (pintype "passive"))
      (node (ref "U3") (pin "6") (pinfunction "GND_6") (pintype "passive"))
      (node (ref "U5") (pin "A2") (pinfunction "GND_A2") (pintype "passive"))
      (node (ref "U5") (pin "B3") (pinfunction "IN-_B3") (pintype "passive"))
      (node (ref "U6") (pin "A2") (pinfunction "GND_A2") (pintype "passive"))
      (node (ref "U6") (pin "B3") (pinfunction "IN-_B3") (pintype "passive"))
    )
    (net (code "34") (name "GND") (class "Default")
      (node (ref "C1") (pin "2") (pinfunction "2_2") (pintype "passive"))
      (node (ref "C12") (pin "1") (pinfunction "1_1") (pintype "passive"))
      (node (ref "C13") (pin "1") (pinfunction "1_1") (pintype "passive"))
      (node (ref "C16") (pin "2") (pinfunction "2_2") (pintype "passive"))
      (node (ref "C17") (pin "1") (pinfunction "1_1") (pintype "passive"))
      (node (ref "C19") (pin "1") (pinfunction "1_1") (pintype "passive"))
      (node (ref "C2") (pin "2") (pinfunction "2_2") (pintype "passive"))
      (node (ref "C20") (pin "1") (pinfunction "1_1") (pintype "passive"))
      (node (ref "C21") (pin "1") (pinfunction "1_1") (pintype "passive"))
      (node (ref "C22") (pin "1") (pinfunction "1_1") (pintype "passive"))
      (node (ref "C23") (pin "1") (pinfunction "1_1") (pintype "passive"))
      (node (ref "C24") (pin "1") (pinfunction "1_1") (pintype "passive"))
      (node (ref "C25") (pin "1") (pinfunction "1_1") (pintype "passive"))
      (node (ref "C26") (pin "1") (pinfunction "1_1") (pintype "passive"))
      (node (ref "C27") (pin "1") (pinfunction "1_1") (pintype "passive"))
      (node (ref "C28") (pin "1") (pinfunction "1_1") (pintype "passive"))
      (node (ref "C29") (pin "1") (pinfunction "1_1") (pintype "passive"))
      (node (ref "C3") (pin "2") (pinfunction "2_2") (pintype "passive"))
      (node (ref "C30") (pin "1") (pinfunction "1_1") (pintype "passive"))
      (node (ref "C31") (pin "1") (pinfunction "1_1") (pintype "passive"))
      (node (ref "C32") (pin "2") (pinfunction "2_2") (pintype "passive"))
      (node (ref "C4") (pin "2") (pinfunction "2_2") (pintype "passive"))
      (node (ref "C6") (pin "1") (pinfunction "1_1") (pintype "passive"))
      (node (ref "C7") (pin "1") (pinfunction "1_1") (pintype "passive"))
      (node (ref "C9") (pin "1") (pinfunction "1_1") (pintype "passive"))
      (node (ref "D5") (pin "2") (pinfunction "A_2") (pintype "passive"))
      (node (ref "D7") (pin "3") (pinfunction "THERMAL_PAD_3") (pintype "passive"))
      (node (ref "D9") (pin "1") (pinfunction "A_1") (pintype "passive"))
      (node (ref "IC1") (pin "18") (pinfunction "DVSS_1_18") (pintype "passive"))
      (node (ref "IC1") (pin "23") (pinfunction "DVSS_2_23") (pintype "passive"))
      (node (ref "IC1") (pin "25") (pinfunction "THERMAL_PAD_25") (pintype "passive"))
      (node (ref "IC2") (pin "5") (pinfunction "VSS_5") (pintype "passive"))
      (node (ref "IC3") (pin "7") (pinfunction "GND_7") (pintype "power_in"))
      (node (ref "J1") (pin "5") (pinfunction "GND_5") (pintype "passive"))
      (node (ref "J1") (pin "S1") (pinfunction "Shield_S1") (pintype "passive"))
      (node (ref "J1") (pin "S2") (pinfunction "Shield_S2") (pintype "passive"))
      (node (ref "J1") (pin "S3") (pinfunction "Shield_S3") (pintype "passive"))
      (node (ref "J1") (pin "S4") (pinfunction "Shield_S4") (pintype "passive"))
      (node (ref "J3") (pin "1") (pinfunction "1_1") (pintype "passive"))
      (node (ref "J4") (pin "6") (pinfunction "6_6") (pintype "passive"))
      (node (ref "J6") (pin "5") (pinfunction "5_5") (pintype "passive"))
      (node (ref "K1") (pin "1") (pinfunction "1_1") (pintype "passive"))
      (node (ref "Q2") (pin "2") (pinfunction "E_2") (pintype "passive"))
      (node (ref "Q3") (pin "1") (pinfunction "S_1") (pintype "passive"))
      (node (ref "Q3") (pin "2") (pinfunction "S_2") (pintype "passive"))
      (node (ref "Q3") (pin "3") (pinfunction "S_3") (pintype "passive"))
      (node (ref "R12") (pin "1") (pinfunction "1_1") (pintype "passive"))
      (node (ref "R19") (pin "2") (pinfunction "2_2") (pintype "passive"))
      (node (ref "R22") (pin "1") (pinfunction "1_1") (pintype "passive"))
      (node (ref "R4") (pin "2") (pinfunction "2_2") (pintype "passive"))
      (node (ref "R8") (pin "1") (pinfunction "1_1") (pintype "passive"))
      (node (ref "Rfbb1") (pin "2") (pinfunction "2_2") (pintype "passive"))
      (node (ref "SW1") (pin "4") (pinfunction "4_4") (pintype "passive"))
      (node (ref "SW2") (pin "4") (pinfunction "4_4") (pintype "passive"))
      (node (ref "U1") (pin "1") (pinfunction "GND_1") (pintype "power_in"))
      (node (ref "U2") (pin "11") (pinfunction "TS_11") (pintype "passive"))
      (node (ref "U2") (pin "12") (pinfunction "RTRICK_12") (pintype "passive"))
      (node (ref "U2") (pin "6") (pinfunction "GND_6") (pintype "power_in"))
      (node (ref "U2") (pin "7") (pinfunction "GND_7") (pintype "power_in"))
      (node (ref "U4") (pin "2") (pinfunction "GND_2") (pintype "power_in"))
      (node (ref "U7") (pin "2") (pinfunction "GND_2") (pintype "power_in"))
      (node (ref "U8") (pin "13") (pinfunction "GND_13") (pintype "power_in"))
      (node (ref "V1") (pin "1") (pinfunction "F-_1") (pintype "power_in"))
      (node (ref "V1") (pin "10") (pinfunction "TSB_10") (pintype "power_in"))
      (node (ref "V1") (pin "2") (pinfunction "F-_2") (pintype "power_in"))
      (node (ref "V1") (pin "31") (pinfunction "PGND_31") (pintype "power_in"))
      (node (ref "V1") (pin "32") (pinfunction "LGND_32") (pintype "power_in"))
      (node (ref "X1") (pin "2") (pinfunction "GND_2") (pintype "power_in"))
    )
    (net (code "35") (name "HV") (class "Default")
      (node (ref "C6") (pin "2") (pinfunction "2_2") (pintype "passive"))
      (node (ref "C8") (pin "2") (pinfunction "2_2") (pintype "passive"))
      (node (ref "D2") (pin "K") (pinfunction "K_K") (pintype "passive"))
      (node (ref "R2") (pin "1") (pinfunction "1_1") (pintype "passive"))
      (node (ref "R23") (pin "1") (pinfunction "1_1") (pintype "passive"))
    )
    (net (code "36") (name "Net-(C5-Pad2)") (class "Default")
      (node (ref "C5") (pin "2") (pinfunction "2_2") (pintype "passive"))
      (node (ref "D2") (pin "A") (pinfunction "A_A") (pintype "passive"))
      (node (ref "D3") (pin "K") (pinfunction "K_K") (pintype "passive"))
    )
    (net (code "37") (name "Net-(C9-Pad2)") (class "Default")
      (node (ref "C9") (pin "2") (pinfunction "2_2") (pintype "passive"))
      (node (ref "D3") (pin "A") (pinfunction "A_A") (pintype "passive"))
      (node (ref "D4") (pin "K") (pinfunction "K_K") (pintype "passive"))
    )
    (net (code "38") (name "Net-(C30-Pad2)") (class "Default")
      (node (ref "C30") (pin "2") (pinfunction "2_2") (pintype "passive"))
      (node (ref "R23") (pin "2") (pinfunction "2_2") (pintype "passive"))
      (node (ref "R24") (pin "1") (pinfunction "1_1") (pintype "passive"))
    )
    (net (code "39") (name "Net-(D1-C)") (class "Default")
      (node (ref "D1") (pin "1") (pinfunction "C_1") (pintype "passive"))
      (node (ref "V1") (pin "34") (pinfunction "F+_34") (pintype "power_in"))
      (node (ref "V1") (pin "35") (pinfunction "F+_35") (pintype "power_in"))
    )
    (net (code "40") (name "Net-(D7-A)") (class "Default")
      (node (ref "D7") (pin "2") (pinfunction "A_2") (pintype "passive"))
      (node (ref "R20") (pin "1") (pinfunction "1_1") (pintype "passive"))
    )
    (net (code "41") (name "Net-(D7-C)") (class "Default")
      (node (ref "D7") (pin "1") (pinfunction "C_1") (pintype "passive"))
      (node (ref "Q3") (pin "5") (pinfunction "D_5") (pintype "passive"))
    )
    (net (code "42") (name "Net-(D8-A)") (class "Default")
      (node (ref "D8") (pin "2") (pinfunction "A_2") (pintype "passive"))
      (node (ref "DS1") (pin "1") (pinfunction "A_1") (pintype "passive"))
      (node (ref "R21") (pin "1") (pinfunction "1_1") (pintype "passive"))
    )
    (net (code "43") (name "Net-(D8-C)") (class "Default")
      (node (ref "D8") (pin "1") (pinfunction "C_1") (pintype "passive"))
      (node (ref "U2") (pin "15") (pinfunction "CHRG_15") (pintype "passive"))
    )
    (net (code "44") (name "Net-(D9-K)") (class "Default")
      (node (ref "D9") (pin "2") (pinfunction "K_2") (pintype "passive"))
      (node (ref "L2") (pin "2") (pinfunction "2_2") (pintype "passive"))
      (node (ref "U2") (pin "3") (pinfunction "LX_3") (pintype "passive"))
      (node (ref "U2") (pin "4") (pinfunction "LX_4") (pintype "passive"))
      (node (ref "U2") (pin "5") (pinfunction "LX_5") (pintype "passive"))
    )
    (net (code "45") (name "Net-(DS1-K)") (class "Default")
      (node (ref "DS1") (pin "2") (pinfunction "K_2") (pintype "passive"))
      (node (ref "U2") (pin "14") (pinfunction "STB_14") (pintype "passive"))
    )
    (net (code "46") (name "Net-(LS1--)") (class "Default")
      (node (ref "LS1") (pin "2") (pinfunction "-_2") (pintype "passive"))
      (node (ref "Q2") (pin "3") (pinfunction "C_3") (pintype "passive"))
    )
    (net (code "47") (name "Net-(U1-RXD)") (class "Default")
      (node (ref "R9") (pin "1") (pinfunction "1_1") (pintype "passive"))
      (node (ref "U1") (pin "3") (pinfunction "RXD_3") (pintype "input"))
    )
    (net (code "48") (name "Net-(U1-TXD)") (class "Default")
      (node (ref "R10") (pin "1") (pinfunction "1_1") (pintype "passive"))
      (node (ref "U1") (pin "2") (pinfunction "TXD_2") (pintype "output"))
    )
    (net (code "49") (name "Net-(U1-V3)") (class "Default")
      (node (ref "C13") (pin "2") (pinfunction "2_2") (pintype "passive"))
      (node (ref "U1") (pin "4") (pinfunction "V3_4") (pintype "power_in"))
    )
    (net (code "50") (name "Net-(U1-XI)") (class "Default")
      (node (ref "U1") (pin "7") (pinfunction "XI_7") (pintype "input"))
      (node (ref "X1") (pin "1") (pinfunction "X1_1") (pintype "passive"))
    )
    (net (code "51") (name "Net-(U1-XO)") (class "Default")
      (node (ref "U1") (pin "8") (pinfunction "XO_8") (pintype "output"))
      (node (ref "X1") (pin "3") (pinfunction "X2_3") (pintype "passive"))
    )
    (net (code "52") (name "Net-(U2-VREG)") (class "Default")
      (node (ref "C16") (pin "1") (pinfunction "1_1") (pintype "passive"))
      (node (ref "U2") (pin "10") (pinfunction "VREG_10") (pintype "passive"))
    )
    (net (code "53") (name "Net-(U2-VS)") (class "Default")
      (node (ref "C3") (pin "1") (pinfunction "1_1") (pintype "passive"))
      (node (ref "L2") (pin "1") (pinfunction "1_1") (pintype "passive"))
      (node (ref "RS1") (pin "2") (pinfunction "2_2") (pintype "passive"))
      (node (ref "U2") (pin "8") (pinfunction "VS_8") (pintype "passive"))
    )
    (net (code "54") (name "Net-(U3-VDD)") (class "Default")
      (node (ref "FB1") (pin "2") (pinfunction "2_2") (pintype "passive"))
      (node (ref "U3") (pin "5") (pinfunction "VDD_5") (pintype "passive"))
    )
    (net (code "55") (name "Net-(U4-FB)") (class "Default")
      (node (ref "C8") (pin "1") (pinfunction "1_1") (pintype "passive"))
      (node (ref "R2") (pin "2") (pinfunction "2_2") (pintype "passive"))
      (node (ref "R4") (pin "1") (pinfunction "1_1") (pintype "passive"))
      (node (ref "U4") (pin "3") (pinfunction "FB_3") (pintype "input"))
    )
    (net (code "56") (name "Net-(U4-SW)") (class "Default")
      (node (ref "C5") (pin "1") (pinfunction "1_1") (pintype "passive"))
      (node (ref "D4") (pin "A") (pinfunction "A_A") (pintype "passive"))
      (node (ref "L1") (pin "2") (pinfunction "2_2") (pintype "passive"))
      (node (ref "U4") (pin "1") (pinfunction "SW_1") (pintype "power_in"))
    )
    (net (code "57") (name "Net-(U5-SHDN)") (class "Default")
      (node (ref "C10") (pin "1") (pinfunction "1_1") (pintype "passive"))
      (node (ref "C11") (pin "1") (pinfunction "1_1") (pintype "passive"))
      (node (ref "R3") (pin "1") (pinfunction "1_1") (pintype "passive"))
      (node (ref "R6") (pin "1") (pinfunction "1_1") (pintype "passive"))
      (node (ref "U5") (pin "A1") (pinfunction "VCC_A1") (pintype "passive"))
      (node (ref "U5") (pin "C2") (pinfunction "SHDN_C2") (pintype "passive"))
    )
    (net (code "58") (name "Net-(U6-SHDN)") (class "Default")
      (node (ref "C14") (pin "1") (pinfunction "1_1") (pintype "passive"))
      (node (ref "C15") (pin "1") (pinfunction "1_1") (pintype "passive"))
      (node (ref "R11") (pin "1") (pinfunction "1_1") (pintype "passive"))
      (node (ref "R14") (pin "1") (pinfunction "1_1") (pintype "passive"))
      (node (ref "U6") (pin "A1") (pinfunction "VCC_A1") (pintype "passive"))
      (node (ref "U6") (pin "C2") (pinfunction "SHDN_C2") (pintype "passive"))
    )
    (net (code "59") (name "Net-(U7-FB)") (class "Default")
      (node (ref "C18") (pin "1") (pinfunction "1_1") (pintype "passive"))
      (node (ref "Rfbb1") (pin "1") (pinfunction "1_1") (pintype "passive"))
      (node (ref "Rfbt1") (pin "2") (pinfunction "2_2") (pintype "passive"))
      (node (ref "U7") (pin "4") (pinfunction "FB_4") (pintype "input"))
    )
    (net (code "60") (name "Net-(U7-SW)") (class "Default")
      (node (ref "L3") (pin "1") (pinfunction "1_1") (pintype "passive"))
      (node (ref "U7") (pin "5") (pinfunction "SW_5") (pintype "power_in"))
    )
    (net (code "61") (name "Net-(V1-OSC)") (class "Default")
      (node (ref "R1") (pin "1") (pinfunction "1_1") (pintype "passive"))
      (node (ref "V1") (pin "24") (pinfunction "OSC_24") (pintype "power_in"))
    )
    (net (code "62") (name "Net-(V1-VH)") (class "Default")
      (node (ref "R24") (pin "2") (pinfunction "2_2") (pintype "passive"))
      (node (ref "V1") (pin "29") (pinfunction "VH_29") (pintype "power_in"))
    )
    (net (code "63") (name "RXD") (class "Default")
      (node (ref "IC1") (pin "4") (pinfunction "P1.5/UCA0RXD/UCA0SOMI/TA1.1/TMS/A5_4") (pintype "passive"))
      (node (ref "J4") (pin "3") (pinfunction "3_3") (pintype "passive"))
      (node (ref "R10") (pin "2") (pinfunction "2_2") (pintype "passive"))
    )
    (net (code "64") (name "TXD") (class "Default")
      (node (ref "IC1") (pin "3") (pinfunction "P1.4/UCA0TXD/UCA0SIMO/TA1.2/TCK/A4/VREF+_3") (pintype "passive"))
      (node (ref "J4") (pin "4") (pinfunction "4_4") (pintype "passive"))
      (node (ref "R9") (pin "2") (pinfunction "2_2") (pintype "passive"))
    )
    (net (code "65") (name "VBAT") (class "Default")
      (node (ref "C17") (pin "2") (pinfunction "2_2") (pintype "passive"))
      (node (ref "C4") (pin "1") (pinfunction "1_1") (pintype "passive"))
      (node (ref "C7") (pin "2") (pinfunction "2_2") (pintype "passive"))
      (node (ref "J3") (pin "2") (pinfunction "2_2") (pintype "passive"))
      (node (ref "L1") (pin "1") (pinfunction "1_1") (pintype "passive"))
      (node (ref "R20") (pin "2") (pinfunction "2_2") (pintype "passive"))
      (node (ref "R5") (pin "2") (pinfunction "2_2") (pintype "passive"))
      (node (ref "RS1") (pin "1") (pinfunction "1_1") (pintype "passive"))
      (node (ref "U2") (pin "9") (pinfunction "BAT_9") (pintype "passive"))
      (node (ref "U4") (pin "4") (pinfunction "EN_4") (pintype "input"))
      (node (ref "U4") (pin "5") (pinfunction "VIN_5") (pintype "power_in"))
      (node (ref "U7") (pin "1") (pinfunction "VIN_1") (pintype "power_in"))
      (node (ref "U7") (pin "3") (pinfunction "EN_3") (pintype "input"))
    )
    (net (code "66") (name "VCC") (class "Default")
      (node (ref "C12") (pin "2") (pinfunction "2_2") (pintype "passive"))
      (node (ref "C2") (pin "1") (pinfunction "1_1") (pintype "passive"))
      (node (ref "C26") (pin "2") (pinfunction "2_2") (pintype "passive"))
      (node (ref "C27") (pin "2") (pinfunction "2_2") (pintype "passive"))
      (node (ref "D5") (pin "1") (pinfunction "C_1") (pintype "passive"))
      (node (ref "J1") (pin "1") (pinfunction "VBUS_1") (pintype "passive"))
      (node (ref "K1") (pin "8") (pinfunction "8_8") (pintype "passive"))
      (node (ref "R11") (pin "2") (pinfunction "2_2") (pintype "passive"))
      (node (ref "R21") (pin "2") (pinfunction "2_2") (pintype "passive"))
      (node (ref "R3") (pin "2") (pinfunction "2_2") (pintype "passive"))
      (node (ref "U1") (pin "16") (pinfunction "VCC_16") (pintype "power_in"))
      (node (ref "U2") (pin "1") (pinfunction "VIN_1") (pintype "power_in"))
      (node (ref "U2") (pin "13") (pinfunction "CS_13") (pintype "passive"))
      (node (ref "U2") (pin "16") (pinfunction "VIN_16") (pintype "power_in"))
      (node (ref "U2") (pin "2") (pinfunction "VIN_2") (pintype "power_in"))
    )
    (net (code "67") (name "unconnected-(IC1-P2.0{slash}XOUT-Pad21)") (class "Default")
      (node (ref "IC1") (pin "21") (pinfunction "P2.0/XOUT_21") (pintype "passive"))
    )
    (net (code "68") (name "unconnected-(IC1-P3.0-Pad12)") (class "Default")
      (node (ref "IC1") (pin "12") (pinfunction "P3.0_12") (pintype "passive"))
    )
    (net (code "69") (name "unconnected-(IC2-EVI-Pad7)") (class "Default")
      (node (ref "IC2") (pin "7") (pinfunction "EVI_7") (pintype "passive"))
    )
    (net (code "70") (name "unconnected-(IC3-CSB-Pad1)") (class "Default")
      (node (ref "IC3") (pin "1") (pinfunction "CSB_1") (pintype "input+no_connect"))
    )
    (net (code "71") (name "unconnected-(IC3-SDO-Pad4)") (class "Default")
      (node (ref "IC3") (pin "4") (pinfunction "SDO_4") (pintype "passive+no_connect"))
    )
    (net (code "72") (name "unconnected-(J1-ID-Pad4)") (class "Default")
      (node (ref "J1") (pin "4") (pinfunction "ID_4") (pintype "passive"))
    )
    (net (code "73") (name "unconnected-(J3-Pad3)") (class "Default")
      (node (ref "J3") (pin "3") (pinfunction "3_3") (pintype "passive"))
    )
    (net (code "74") (name "unconnected-(J3-Pad4)") (class "Default")
      (node (ref "J3") (pin "4") (pinfunction "4_4") (pintype "passive"))
    )
    (net (code "75") (name "unconnected-(J4-PadMP1)") (class "Default")
      (node (ref "J4") (pin "MP1") (pinfunction "MP1_MP1") (pintype "passive"))
    )
    (net (code "76") (name "unconnected-(J4-PadMP2)") (class "Default")
      (node (ref "J4") (pin "MP2") (pinfunction "MP2_MP2") (pintype "passive"))
    )
    (net (code "77") (name "unconnected-(LS1-NC-Pad3)") (class "Default")
      (node (ref "LS1") (pin "3") (pinfunction "NC_3") (pintype "passive"))
    )
    (net (code "78") (name "unconnected-(SPK_L-Pad3)") (class "Default")
      (node (ref "SPK_L") (pin "3") (pinfunction "3_3") (pintype "passive+no_connect"))
    )
    (net (code "79") (name "unconnected-(SPK_L-Pad4)") (class "Default")
      (node (ref "SPK_L") (pin "4") (pinfunction "4_4") (pintype "passive+no_connect"))
    )
    (net (code "80") (name "unconnected-(SPK_R-Pad3)") (class "Default")
      (node (ref "SPK_R") (pin "3") (pinfunction "3_3") (pintype "passive+no_connect"))
    )
    (net (code "81") (name "unconnected-(SPK_R-Pad4)") (class "Default")
      (node (ref "SPK_R") (pin "4") (pinfunction "4_4") (pintype "passive+no_connect"))
    )
    (net (code "82") (name "unconnected-(SW1-Pad2)") (class "Default")
      (node (ref "SW1") (pin "2") (pinfunction "2_2") (pintype "passive"))
    )
    (net (code "83") (name "unconnected-(SW1-Pad3)") (class "Default")
      (node (ref "SW1") (pin "3") (pinfunction "3_3") (pintype "passive"))
    )
    (net (code "84") (name "unconnected-(SW2-Pad2)") (class "Default")
      (node (ref "SW2") (pin "2") (pinfunction "2_2") (pintype "passive"))
    )
    (net (code "85") (name "unconnected-(SW2-Pad3)") (class "Default")
      (node (ref "SW2") (pin "3") (pinfunction "3_3") (pintype "passive"))
    )
    (net (code "86") (name "unconnected-(U1-RS232-Pad15)") (class "Default")
      (node (ref "U1") (pin "15") (pinfunction "RS232_15") (pintype "input"))
    )
    (net (code "87") (name "unconnected-(U1-~{CTS}-Pad9)") (class "Default")
      (node (ref "U1") (pin "9") (pinfunction "~{CTS}_9") (pintype "input+no_connect"))
    )
    (net (code "88") (name "unconnected-(U1-~{DCD}-Pad12)") (class "Default")
      (node (ref "U1") (pin "12") (pinfunction "~{DCD}_12") (pintype "input+no_connect"))
    )
    (net (code "89") (name "unconnected-(U1-~{DSR}-Pad10)") (class "Default")
      (node (ref "U1") (pin "10") (pinfunction "~{DSR}_10") (pintype "input+no_connect"))
    )
    (net (code "90") (name "unconnected-(U1-~{DTR}-Pad13)") (class "Default")
      (node (ref "U1") (pin "13") (pinfunction "~{DTR}_13") (pintype "output"))
    )
    (net (code "91") (name "unconnected-(U1-~{RI}-Pad11)") (class "Default")
      (node (ref "U1") (pin "11") (pinfunction "~{RI}_11") (pintype "input+no_connect"))
    )
    (net (code "92") (name "unconnected-(U1-~{RTS}-Pad14)") (class "Default")
      (node (ref "U1") (pin "14") (pinfunction "~{RTS}_14") (pintype "output"))
    )
    (net (code "93") (name "unconnected-(U3-RCK-Pad9)") (class "Default")
      (node (ref "U3") (pin "9") (pinfunction "RCK_9") (pintype "passive"))
    )
    (net (code "94") (name "unconnected-(U8A-~{INT}{slash}SQW-Pad3)") (class "Default")
      (node (ref "U8") (pin "3") (pinfunction "~{INT}/SQW_3") (pintype "open_collector+no_connect"))
    )
    (net (code "95") (name "unconnected-(U8A-~{RST}-Pad4)") (class "Default")
      (node (ref "U8") (pin "4") (pinfunction "~{RST}_4") (pintype "bidirectional+no_connect"))
    )
    (net (code "96") (name "unconnected-(U8B-NC-Pad5)") (class "Default")
      (node (ref "U8") (pin "5") (pinfunction "NC_5") (pintype "passive+no_connect"))
    )
    (net (code "97") (name "unconnected-(U8B-NC-Pad6)") (class "Default")
      (node (ref "U8") (pin "6") (pinfunction "NC_6") (pintype "passive+no_connect"))
    )
    (net (code "98") (name "unconnected-(U8B-NC-Pad7)") (class "Default")
      (node (ref "U8") (pin "7") (pinfunction "NC_7") (pintype "passive+no_connect"))
    )
    (net (code "99") (name "unconnected-(U8B-NC-Pad8)") (class "Default")
      (node (ref "U8") (pin "8") (pinfunction "NC_8") (pintype "passive+no_connect"))
    )
    (net (code "100") (name "unconnected-(U8B-NC-Pad9)") (class "Default")
      (node (ref "U8") (pin "9") (pinfunction "NC_9") (pintype "passive+no_connect"))
    )
    (net (code "101") (name "unconnected-(U8B-NC-Pad10)") (class "Default")
      (node (ref "U8") (pin "10") (pinfunction "NC_10") (pintype "passive+no_connect"))
    )
    (net (code "102") (name "unconnected-(U8B-NC-Pad11)") (class "Default")
      (node (ref "U8") (pin "11") (pinfunction "NC_11") (pintype "passive+no_connect"))
    )
    (net (code "103") (name "unconnected-(U8B-NC-Pad12)") (class "Default")
      (node (ref "U8") (pin "12") (pinfunction "NC_12") (pintype "passive+no_connect"))
    )
    (net (code "104") (name "unconnected-(V1-1G-Pad28)") (class "Default")
      (node (ref "V1") (pin "28") (pinfunction "1G_28") (pintype "power_in+no_connect"))
    )
    (net (code "105") (name "unconnected-(V1-1G-Pad30)") (class "Default")
      (node (ref "V1") (pin "30") (pinfunction "1G_30") (pintype "power_in+no_connect"))
    )
    (net (code "106") (name "unconnected-(V1-2G-Pad25)") (class "Default")
      (node (ref "V1") (pin "25") (pinfunction "2G_25") (pintype "power_in+no_connect"))
    )
    (net (code "107") (name "unconnected-(V1-2G-Pad26)") (class "Default")
      (node (ref "V1") (pin "26") (pinfunction "2G_26") (pintype "power_in+no_connect"))
    )
    (net (code "108") (name "unconnected-(V1-3G-Pad21)") (class "Default")
      (node (ref "V1") (pin "21") (pinfunction "3G_21") (pintype "power_in+no_connect"))
    )
    (net (code "109") (name "unconnected-(V1-3G-Pad23)") (class "Default")
      (node (ref "V1") (pin "23") (pinfunction "3G_23") (pintype "power_in+no_connect"))
    )
    (net (code "110") (name "unconnected-(V1-4G-Pad18)") (class "Default")
      (node (ref "V1") (pin "18") (pinfunction "4G_18") (pintype "power_in+no_connect"))
    )
    (net (code "111") (name "unconnected-(V1-4G-Pad19)") (class "Default")
      (node (ref "V1") (pin "19") (pinfunction "4G_19") (pintype "power_in+no_connect"))
    )
    (net (code "112") (name "unconnected-(V1-5G-Pad14)") (class "Default")
      (node (ref "V1") (pin "14") (pinfunction "5G_14") (pintype "power_in+no_connect"))
    )
    (net (code "113") (name "unconnected-(V1-5G-Pad16)") (class "Default")
      (node (ref "V1") (pin "16") (pinfunction "5G_16") (pintype "power_in+no_connect"))
    )
    (net (code "114") (name "unconnected-(V1-6G-Pad11)") (class "Default")
      (node (ref "V1") (pin "11") (pinfunction "6G_11") (pintype "power_in+no_connect"))
    )
    (net (code "115") (name "unconnected-(V1-6G-Pad13)") (class "Default")
      (node (ref "V1") (pin "13") (pinfunction "6G_13") (pintype "power_in+no_connect"))
    )
    (net (code "116") (name "unconnected-(V1-7G-Pad8)") (class "Default")
      (node (ref "V1") (pin "8") (pinfunction "7G_8") (pintype "power_in+no_connect"))
    )
    (net (code "117") (name "unconnected-(V1-7G-Pad9)") (class "Default")
      (node (ref "V1") (pin "9") (pinfunction "7G_9") (pintype "power_in+no_connect"))
    )
    (net (code "118") (name "unconnected-(V1-8G-Pad4)") (class "Default")
      (node (ref "V1") (pin "4") (pinfunction "8G_4") (pintype "power_in+no_connect"))
    )
    (net (code "119") (name "unconnected-(V1-8G-Pad6)") (class "Default")
      (node (ref "V1") (pin "6") (pinfunction "8G_6") (pintype "power_in+no_connect"))
    )
    (net (code "120") (name "unconnected-(V1-NC-Pad5)") (class "Default")
      (node (ref "V1") (pin "5") (pinfunction "NC_5") (pintype "power_in+no_connect"))
    )
    (net (code "121") (name "unconnected-(V1-NC-Pad7)") (class "Default")
      (node (ref "V1") (pin "7") (pinfunction "NC_7") (pintype "power_in+no_connect"))
    )
    (net (code "122") (name "unconnected-(V1-TSA-Pad12)") (class "Default")
      (node (ref "V1") (pin "12") (pinfunction "TSA_12") (pintype "power_in+no_connect"))
    )
  )
)
